# RGBM-07.net
KiCad netlist of a schematic drawn in Altium Designer
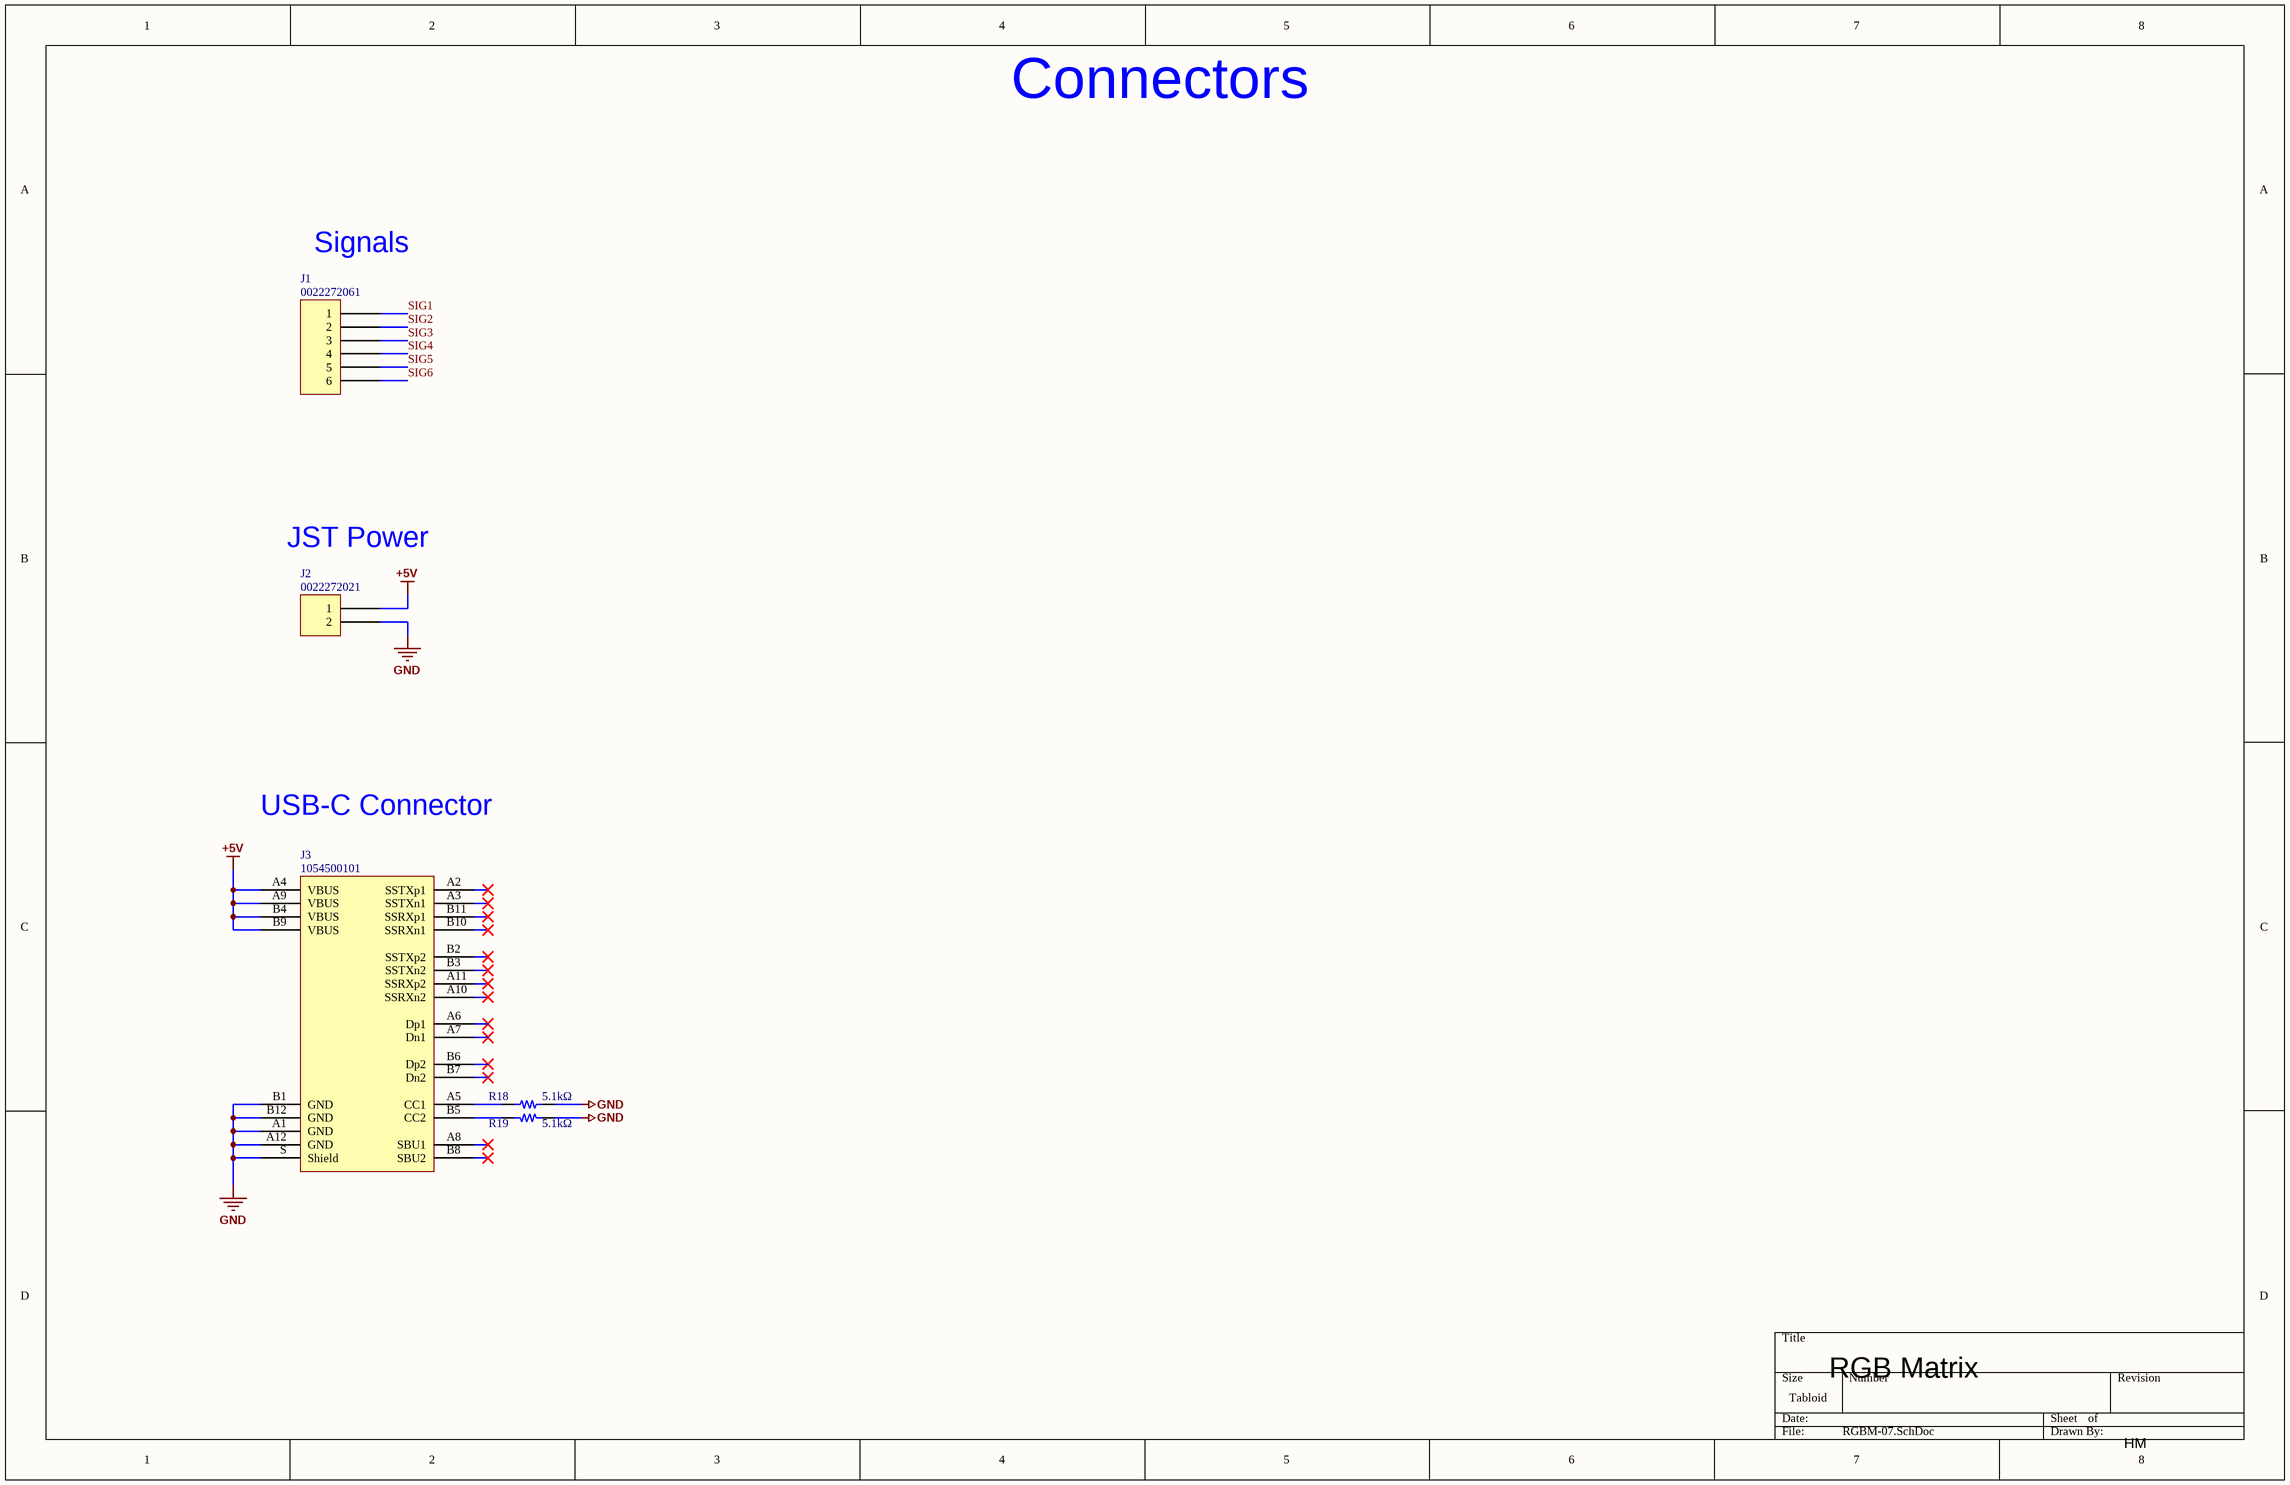
[diagram p0: RGBM-07.SchDoc]

(export (version "E")
  (design (tool "Eeschema 10.0.6"))
  (components
    (comp (ref "J1")
      (value "0022272061")
      (footprint "MOLEX KK 0022272061")
      (description "CONN HEADER VERT 6POS 2.54MM")
      (fields (field (name "MANUFACTURER") "Molex"))
      (libsource (lib "Celestial Altium Library - altium_library") (part "6 Pin"))
    )
    (comp (ref "J2")
      (value "0022272021")
      (footprint "MOLEX KK 0022272021")
      (description "CONN HEADER VERT 2POS 2.54MM")
      (fields (field (name "MANUFACTURER") "Molex"))
      (libsource (lib "Celestial Altium Library - altium_library") (part "2 Pin"))
    )
    (comp (ref "J3")
      (value "1054500101")
      (footprint "Molex 1054500101")
      (description "CONN RCP USB3.1 TYPEC 24P SMD RA")
      (fields (field (name "MANUFACTURER") "Molex"))
      (libsource (lib "Celestial Altium Library - altium_library") (part "USB 3.0 Type C"))
    )
    (comp (ref "R18")
      (value "5.1kΩ")
      (footprint "RES 0603_1608")
      (description "RES SMD 5.1K OHM 1% 1/10W 0603")
      (fields (field (name "PART NUMBER") "AC0603FR-075K1L") (field (name "MANUFACTURER") "Yageo"))
      (libsource (lib "Celestial Altium Library - altium_library") (part "Resistor"))
    )
    (comp (ref "R19")
      (value "5.1kΩ")
      (footprint "RES 0603_1608")
      (description "RES SMD 5.1K OHM 1% 1/10W 0603")
      (fields (field (name "PART NUMBER") "AC0603FR-075K1L") (field (name "MANUFACTURER") "Yageo"))
      (libsource (lib "Celestial Altium Library - altium_library") (part "Resistor"))
    )
  )
  (nets
    (net (code "1") (name "+5V") (class "Default")
      (node (ref "J2") (pin "1") (pinfunction "1_1") (pintype "passive"))
      (node (ref "J3") (pin "A4") (pinfunction "VBUS_A4") (pintype "passive"))
      (node (ref "J3") (pin "A9") (pinfunction "VBUS_A9") (pintype "passive"))
      (node (ref "J3") (pin "B4") (pinfunction "VBUS_B4") (pintype "passive"))
      (node (ref "J3") (pin "B9") (pinfunction "VBUS_B9") (pintype "passive"))
    )
    (net (code "2") (name "/SIG1") (class "Default")
      (node (ref "J1") (pin "1") (pinfunction "1_1") (pintype "passive"))
    )
    (net (code "3") (name "/SIG2") (class "Default")
      (node (ref "J1") (pin "2") (pinfunction "2_2") (pintype "passive"))
    )
    (net (code "4") (name "/SIG3") (class "Default")
      (node (ref "J1") (pin "3") (pinfunction "3_3") (pintype "passive"))
    )
    (net (code "5") (name "/SIG4") (class "Default")
      (node (ref "J1") (pin "4") (pinfunction "4_4") (pintype "passive"))
    )
    (net (code "6") (name "/SIG5") (class "Default")
      (node (ref "J1") (pin "5") (pinfunction "5_5") (pintype "passive"))
    )
    (net (code "7") (name "/SIG6") (class "Default")
      (node (ref "J1") (pin "6") (pinfunction "6_6") (pintype "passive"))
    )
    (net (code "8") (name "GND") (class "Default")
      (node (ref "J2") (pin "2") (pinfunction "2_2") (pintype "passive"))
      (node (ref "J3") (pin "A1") (pinfunction "GND_A1") (pintype "passive"))
      (node (ref "J3") (pin "A12") (pinfunction "GND_A12") (pintype "passive"))
      (node (ref "J3") (pin "B1") (pinfunction "GND_B1") (pintype "passive"))
      (node (ref "J3") (pin "B12") (pinfunction "GND_B12") (pintype "passive"))
      (node (ref "J3") (pin "S") (pinfunction "Shield_S") (pintype "passive"))
      (node (ref "R18") (pin "2") (pinfunction "2_2") (pintype "passive"))
      (node (ref "R19") (pin "2") (pinfunction "2_2") (pintype "passive"))
    )
    (net (code "9") (name "Net-(J3-CC1)") (class "Default")
      (node (ref "J3") (pin "A5") (pinfunction "CC1_A5") (pintype "passive"))
      (node (ref "R18") (pin "1") (pinfunction "1_1") (pintype "passive"))
    )
    (net (code "10") (name "Net-(J3-CC2)") (class "Default")
      (node (ref "J3") (pin "B5") (pinfunction "CC2_B5") (pintype "passive"))
      (node (ref "R19") (pin "1") (pinfunction "1_1") (pintype "passive"))
    )
    (net (code "11") (name "unconnected-(J3-Dn1-PadA7)") (class "Default")
      (node (ref "J3") (pin "A7") (pinfunction "Dn1_A7") (pintype "passive+no_connect"))
    )
    (net (code "12") (name "unconnected-(J3-Dn2-PadB7)") (class "Default")
      (node (ref "J3") (pin "B7") (pinfunction "Dn2_B7") (pintype "passive+no_connect"))
    )
    (net (code "13") (name "unconnected-(J3-Dp1-PadA6)") (class "Default")
      (node (ref "J3") (pin "A6") (pinfunction "Dp1_A6") (pintype "passive+no_connect"))
    )
    (net (code "14") (name "unconnected-(J3-Dp2-PadB6)") (class "Default")
      (node (ref "J3") (pin "B6") (pinfunction "Dp2_B6") (pintype "passive+no_connect"))
    )
    (net (code "15") (name "unconnected-(J3-SBU1-PadA8)") (class "Default")
      (node (ref "J3") (pin "A8") (pinfunction "SBU1_A8") (pintype "passive+no_connect"))
    )
    (net (code "16") (name "unconnected-(J3-SBU2-PadB8)") (class "Default")
      (node (ref "J3") (pin "B8") (pinfunction "SBU2_B8") (pintype "passive+no_connect"))
    )
    (net (code "17") (name "unconnected-(J3-SSRXn1-PadB10)") (class "Default")
      (node (ref "J3") (pin "B10") (pinfunction "SSRXn1_B10") (pintype "passive+no_connect"))
    )
    (net (code "18") (name "unconnected-(J3-SSRXn2-PadA10)") (class "Default")
      (node (ref "J3") (pin "A10") (pinfunction "SSRXn2_A10") (pintype "passive+no_connect"))
    )
    (net (code "19") (name "unconnected-(J3-SSRXp1-PadB11)") (class "Default")
      (node (ref "J3") (pin "B11") (pinfunction "SSRXp1_B11") (pintype "passive+no_connect"))
    )
    (net (code "20") (name "unconnected-(J3-SSRXp2-PadA11)") (class "Default")
      (node (ref "J3") (pin "A11") (pinfunction "SSRXp2_A11") (pintype "passive+no_connect"))
    )
    (net (code "21") (name "unconnected-(J3-SSTXn1-PadA3)") (class "Default")
      (node (ref "J3") (pin "A3") (pinfunction "SSTXn1_A3") (pintype "passive+no_connect"))
    )
    (net (code "22") (name "unconnected-(J3-SSTXn2-PadB3)") (class "Default")
      (node (ref "J3") (pin "B3") (pinfunction "SSTXn2_B3") (pintype "passive+no_connect"))
    )
    (net (code "23") (name "unconnected-(J3-SSTXp1-PadA2)") (class "Default")
      (node (ref "J3") (pin "A2") (pinfunction "SSTXp1_A2") (pintype "passive+no_connect"))
    )
    (net (code "24") (name "unconnected-(J3-SSTXp2-PadB2)") (class "Default")
      (node (ref "J3") (pin "B2") (pinfunction "SSTXp2_B2") (pintype "passive+no_connect"))
    )
  )
)
